# iSystem-boards.net
KiCad netlist of a schematic drawn in Altium Designer
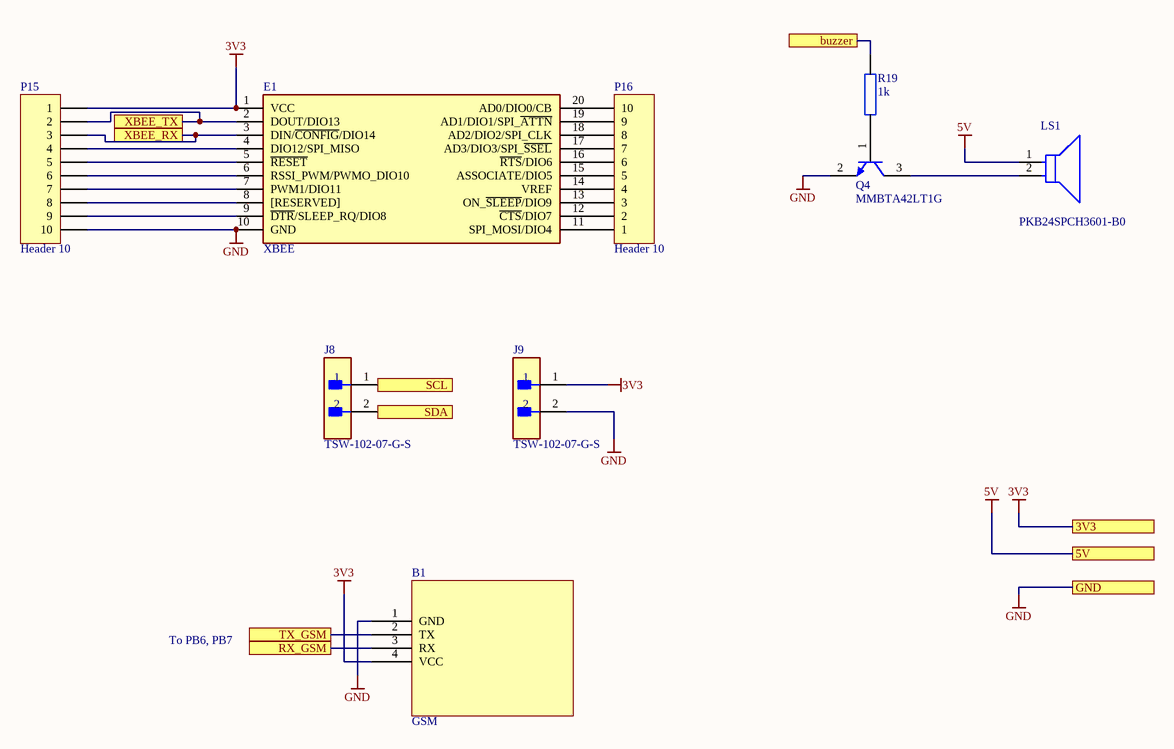
[diagram p0: iSystem-boards.SchDoc]

(export (version "E")
  (design (tool "Eeschema 10.0.6"))
  (components
    (comp (ref "B1")
      (value "GSM")
      (footprint "GSM")
      (description "3V3")
      (libsource (lib "Götterdämmerung") (part "GSM"))
    )
    (comp (ref "E1") (value "XBEE") (footprint "XBEE") (libsource (lib "Götterdämmerung") (part "XBEE")))
    (comp (ref "J8")
      (value "TSW-102-07-G-S")
      (footprint "FP-TSW-102-07-G-S-MFG")
      (description "CONN HEADER VERT 2POS 2.54MM")
      (fields
        (field (name "MANUFACTURER") "Samtec")
        (field (name "OCTOPART") "https://octopart.com/tsw-102-07-g-s-samtec-272197")
      )
      (libsource (lib "Altium Content Vault") (part "3bc925449376181038e59eaffc5286c"))
    )
    (comp (ref "J9")
      (value "TSW-102-07-G-S")
      (footprint "FP-TSW-102-07-G-S-MFG")
      (description "CONN HEADER VERT 2POS 2.54MM")
      (fields
        (field (name "MANUFACTURER") "Samtec")
        (field (name "OCTOPART") "https://octopart.com/tsw-102-07-g-s-samtec-272197")
      )
      (libsource (lib "Altium Content Vault") (part "3bc925449376181038e59eaffc5286c"))
    )
    (comp (ref "LS1")
      (value "PKB24SPCH3601-B0")
      (footprint "FP-PKB24SPCH3601-B0-MFG")
      (description "AUDIO PIEZO TRANSDUCER 3-15V TH")
      (libsource (lib "Altium Content Vault") (part "1973c4b650225fd2ddacaff6b763965"))
    )
    (comp (ref "P15")
      (value "Header 10")
      (footprint "HDR1X10")
      (description "Header, 10-Pin")
      (fields (field (name "PUBLISHER") "Altium Limited"))
      (libsource (lib "") (part "Header 10_1"))
    )
    (comp (ref "P16")
      (value "Header 10")
      (footprint "HDR1X10")
      (description "Header, 10-Pin")
      (fields (field (name "PUBLISHER") "Altium Limited"))
      (libsource (lib "Miscellaneous Connectors") (part "Header 10"))
    )
    (comp (ref "Q4")
      (value "MMBTA42LT1G")
      (footprint "ONSC-SOT-23-3-318-08_V")
      (description "High Voltage Transistor, NPN Silicon, 3-Pin SOT-23, Pb-Free, Tape and Reel")
      (fields (field (name "MANUFACTURER") "On Semiconductor"))
      (libsource (lib "Altium Content Vault") (part "ONSC-NPN-B1E2C3-3"))
    )
    (comp (ref "R19")
      (value "1k")
      (footprint "0603")
      (description "Resistor")
      (libsource (lib "General") (part "Resistor"))
    )
  )
  (nets
    (net (code "1") (name "/RX_GSM") (class "Default")
      (node (ref "B1") (pin "3") (pinfunction "RX_3") (pintype "passive"))
    )
    (net (code "2") (name "/SCL") (class "Default")
      (node (ref "J8") (pin "1") (pinfunction "1_1") (pintype "passive"))
    )
    (net (code "3") (name "/SDA") (class "Default")
      (node (ref "J8") (pin "2") (pinfunction "2_2") (pintype "passive"))
    )
    (net (code "4") (name "/TX_GSM") (class "Default")
      (node (ref "B1") (pin "2") (pinfunction "TX_2") (pintype "passive"))
    )
    (net (code "5") (name "/XBEE_RX") (class "Default")
      (node (ref "E1") (pin "3") (pinfunction "DIN/~{CONFIG}/DIO14_3") (pintype "passive"))
      (node (ref "P15") (pin "3") (pinfunction "3_3") (pintype "passive"))
    )
    (net (code "6") (name "/XBEE_TX") (class "Default")
      (node (ref "E1") (pin "2") (pinfunction "DOUT/DIO13_2") (pintype "passive"))
      (node (ref "P15") (pin "2") (pinfunction "2_2") (pintype "passive"))
    )
    (net (code "7") (name "/buzzer") (class "Default") (node (ref "R19") (pin "2") (pintype "passive")))
    (net (code "8") (name "3V3") (class "Default")
      (node (ref "B1") (pin "4") (pinfunction "VCC_4") (pintype "passive"))
      (node (ref "E1") (pin "1") (pinfunction "VCC_1") (pintype "passive"))
      (node (ref "J9") (pin "1") (pinfunction "1_1") (pintype "passive"))
      (node (ref "P15") (pin "1") (pinfunction "1_1") (pintype "passive"))
    )
    (net (code "9") (name "5V") (class "Default")
      (node (ref "LS1") (pin "1") (pinfunction "C_1") (pintype "passive"))
    )
    (net (code "10") (name "GND") (class "Default")
      (node (ref "B1") (pin "1") (pinfunction "GND_1") (pintype "passive"))
      (node (ref "E1") (pin "10") (pinfunction "GND_10") (pintype "passive"))
      (node (ref "J9") (pin "2") (pinfunction "2_2") (pintype "passive"))
      (node (ref "P15") (pin "10") (pinfunction "10_10") (pintype "passive"))
      (node (ref "Q4") (pin "2") (pinfunction "E_2") (pintype "passive"))
    )
    (net (code "11") (name "Net-(E1-AD0{slash}DIO0{slash}CB)") (class "Default")
      (node (ref "E1") (pin "20") (pinfunction "AD0/DIO0/CB_20") (pintype "passive"))
      (node (ref "P16") (pin "10") (pinfunction "10_10") (pintype "passive"))
    )
    (net (code "12") (name "Net-(E1-AD1{slash}DIO1{slash}SPI_~{ATTN})") (class "Default")
      (node (ref "E1") (pin "19") (pinfunction "AD1/DIO1/SPI_~{ATTN}_19") (pintype "passive"))
      (node (ref "P16") (pin "9") (pinfunction "9_9") (pintype "passive"))
    )
    (net (code "13") (name "Net-(E1-AD2{slash}DIO2{slash}SPI_CLK)") (class "Default")
      (node (ref "E1") (pin "18") (pinfunction "AD2/DIO2/SPI_CLK_18") (pintype "passive"))
      (node (ref "P16") (pin "8") (pinfunction "8_8") (pintype "passive"))
    )
    (net (code "14") (name "Net-(E1-AD3{slash}DIO3{slash}SPI_~{SSEL})") (class "Default")
      (node (ref "E1") (pin "17") (pinfunction "AD3/DIO3/SPI_~{SSEL}_17") (pintype "passive"))
      (node (ref "P16") (pin "7") (pinfunction "7_7") (pintype "passive"))
    )
    (net (code "15") (name "Net-(E1-ASSOCIATE{slash}DIO5)") (class "Default")
      (node (ref "E1") (pin "15") (pinfunction "ASSOCIATE/DIO5_15") (pintype "passive"))
      (node (ref "P16") (pin "5") (pinfunction "5_5") (pintype "passive"))
    )
    (net (code "16") (name "Net-(E1-DIO12{slash}SPI_MISO)") (class "Default")
      (node (ref "E1") (pin "4") (pinfunction "DIO12/SPI_MISO_4") (pintype "passive"))
      (node (ref "P15") (pin "4") (pinfunction "4_4") (pintype "passive"))
    )
    (net (code "17") (name "Net-(E1-ON_~{SLEEP}{slash}DIO9)") (class "Default")
      (node (ref "E1") (pin "13") (pinfunction "ON_~{SLEEP}/DIO9_13") (pintype "passive"))
      (node (ref "P16") (pin "3") (pinfunction "3_3") (pintype "passive"))
    )
    (net (code "18") (name "Net-(E1-PWM1{slash}DIO11)") (class "Default")
      (node (ref "E1") (pin "7") (pinfunction "PWM1/DIO11_7") (pintype "passive"))
      (node (ref "P15") (pin "7") (pinfunction "7_7") (pintype "passive"))
    )
    (net (code "19") (name "Net-(E1-RSSI_PWM{slash}PWMO_DIO10)") (class "Default")
      (node (ref "E1") (pin "6") (pinfunction "RSSI_PWM/PWMO_DIO10_6") (pintype "passive"))
      (node (ref "P15") (pin "6") (pinfunction "6_6") (pintype "passive"))
    )
    (net (code "20") (name "Net-(E1-SPI_MOSI{slash}DIO4)") (class "Default")
      (node (ref "E1") (pin "11") (pinfunction "SPI_MOSI/DIO4_11") (pintype "passive"))
      (node (ref "P16") (pin "1") (pinfunction "1_1") (pintype "passive"))
    )
    (net (code "21") (name "Net-(E1-VREF)") (class "Default")
      (node (ref "E1") (pin "14") (pinfunction "VREF_14") (pintype "passive"))
      (node (ref "P16") (pin "4") (pinfunction "4_4") (pintype "passive"))
    )
    (net (code "22") (name "Net-(E1-[RESERVED])") (class "Default")
      (node (ref "E1") (pin "8") (pinfunction "[RESERVED]_8") (pintype "passive"))
      (node (ref "P15") (pin "8") (pinfunction "8_8") (pintype "passive"))
    )
    (net (code "23") (name "Net-(E1-~{CTS}{slash}DIO7)") (class "Default")
      (node (ref "E1") (pin "12") (pinfunction "~{CTS}/DIO7_12") (pintype "passive"))
      (node (ref "P16") (pin "2") (pinfunction "2_2") (pintype "passive"))
    )
    (net (code "24") (name "Net-(E1-~{DTR}{slash}SLEEP_RQ{slash}DIO8)") (class "Default")
      (node (ref "E1") (pin "9") (pinfunction "~{DTR}/SLEEP_RQ/DIO8_9") (pintype "passive"))
      (node (ref "P15") (pin "9") (pinfunction "9_9") (pintype "passive"))
    )
    (net (code "25") (name "Net-(E1-~{RESET})") (class "Default")
      (node (ref "E1") (pin "5") (pinfunction "~{RESET}_5") (pintype "passive"))
      (node (ref "P15") (pin "5") (pinfunction "5_5") (pintype "passive"))
    )
    (net (code "26") (name "Net-(E1-~{RTS}{slash}DIO6)") (class "Default")
      (node (ref "E1") (pin "16") (pinfunction "~{RTS}/DIO6_16") (pintype "passive"))
      (node (ref "P16") (pin "6") (pinfunction "6_6") (pintype "passive"))
    )
    (net (code "27") (name "Net-(LS1-A)") (class "Default")
      (node (ref "LS1") (pin "2") (pinfunction "A_2") (pintype "passive"))
      (node (ref "Q4") (pin "3") (pinfunction "C_3") (pintype "passive"))
    )
    (net (code "28") (name "Net-(Q4-B)") (class "Default")
      (node (ref "Q4") (pin "1") (pinfunction "B_1") (pintype "passive"))
      (node (ref "R19") (pin "1") (pintype "passive"))
    )
  )
)
